# HIC_Board.net
KiCad netlist of a schematic drawn in EAGLE
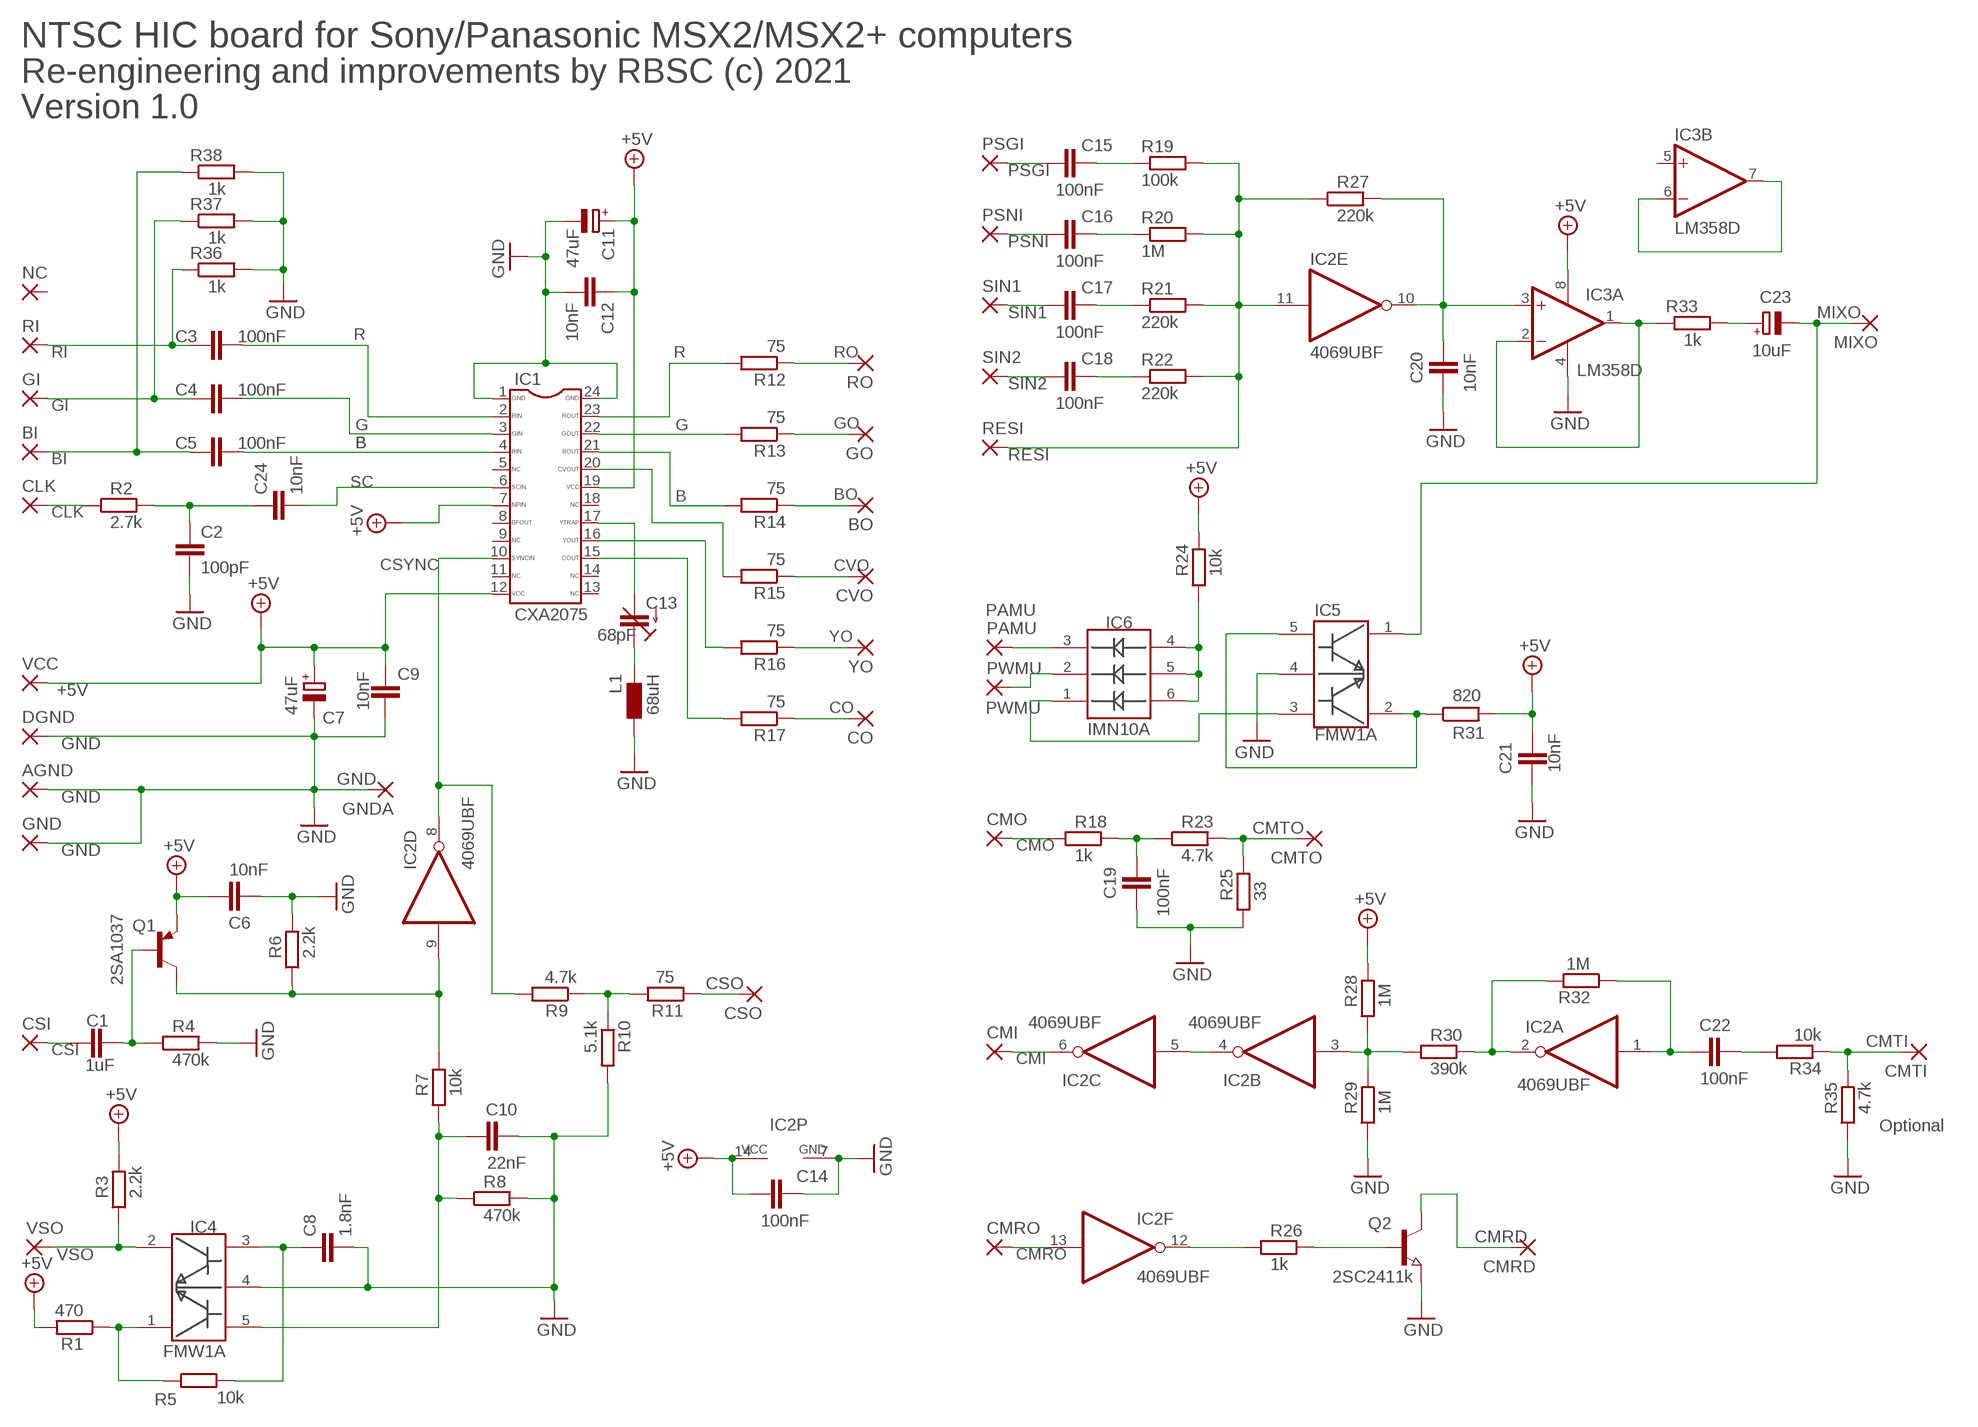
[diagram p0: schematic, sheet 1]

(export (version "E")
  (design (tool "Eeschema 10.0.6"))
  (components
    (comp (ref "AGND")
      (value "HICPADSMD")
      (footprint "eagle-import:SMD1,27-2,54")
      (libsource (lib "eagle-import") (part "HICPADSMD"))
    )
    (comp (ref "BI")
      (value "HICPADSMD")
      (footprint "eagle-import:SMD1,27-2,54")
      (libsource (lib "eagle-import") (part "HICPADSMD"))
    )
    (comp (ref "BO")
      (value "HICPADSMD")
      (footprint "eagle-import:SMD1,27-2,54")
      (libsource (lib "eagle-import") (part "HICPADSMD"))
    )
    (comp (ref "C1")
      (value "1uF")
      (footprint "eagle-import:C1210")
      (libsource (lib "eagle-import") (part "C-EUC1210"))
    )
    (comp (ref "C2")
      (value "100pF")
      (footprint "eagle-import:C0805")
      (libsource (lib "eagle-import") (part "C-EUC0805"))
    )
    (comp (ref "C3")
      (value "100nF")
      (footprint "eagle-import:C0805")
      (libsource (lib "eagle-import") (part "C-EUC0805"))
    )
    (comp (ref "C4")
      (value "100nF")
      (footprint "eagle-import:C0805")
      (libsource (lib "eagle-import") (part "C-EUC0805"))
    )
    (comp (ref "C5")
      (value "100nF")
      (footprint "eagle-import:C0805")
      (libsource (lib "eagle-import") (part "C-EUC0805"))
    )
    (comp (ref "C6")
      (value "10nF")
      (footprint "eagle-import:C0805")
      (libsource (lib "eagle-import") (part "C-EUC0805"))
    )
    (comp (ref "C7")
      (value "47uF")
      (footprint "eagle-import:SMC_B")
      (libsource (lib "eagle-import") (part "CPOL-EUSMCB"))
    )
    (comp (ref "C8")
      (value "1.8nF")
      (footprint "eagle-import:C0805")
      (libsource (lib "eagle-import") (part "C-EUC0805"))
    )
    (comp (ref "C9")
      (value "10nF")
      (footprint "eagle-import:C0805")
      (libsource (lib "eagle-import") (part "C-EUC0805"))
    )
    (comp (ref "C10")
      (value "22nF")
      (footprint "eagle-import:C0805")
      (libsource (lib "eagle-import") (part "C-EUC0805"))
    )
    (comp (ref "C11")
      (value "47uF")
      (footprint "eagle-import:SMC_B")
      (libsource (lib "eagle-import") (part "CPOL-EUSMCB"))
    )
    (comp (ref "C12")
      (value "10nF")
      (footprint "eagle-import:C0805")
      (libsource (lib "eagle-import") (part "C-EUC0805"))
    )
    (comp (ref "C13")
      (value "68pF")
      (footprint "eagle-import:CTRIMTZ03")
      (libsource (lib "eagle-import") (part "C-TRIMMTZ03"))
    )
    (comp (ref "C14")
      (value "100nF")
      (footprint "eagle-import:C0805")
      (libsource (lib "eagle-import") (part "C-EUC0805"))
    )
    (comp (ref "C15")
      (value "100nF")
      (footprint "eagle-import:C0805")
      (libsource (lib "eagle-import") (part "C-EUC0805"))
    )
    (comp (ref "C16")
      (value "100nF")
      (footprint "eagle-import:C0805")
      (libsource (lib "eagle-import") (part "C-EUC0805"))
    )
    (comp (ref "C17")
      (value "100nF")
      (footprint "eagle-import:C0805")
      (libsource (lib "eagle-import") (part "C-EUC0805"))
    )
    (comp (ref "C18")
      (value "100nF")
      (footprint "eagle-import:C0805")
      (libsource (lib "eagle-import") (part "C-EUC0805"))
    )
    (comp (ref "C19")
      (value "100nF")
      (footprint "eagle-import:C0805")
      (libsource (lib "eagle-import") (part "C-EUC0805"))
    )
    (comp (ref "C20")
      (value "10nF")
      (footprint "eagle-import:C0805")
      (libsource (lib "eagle-import") (part "C-EUC0805"))
    )
    (comp (ref "C21")
      (value "10nF")
      (footprint "eagle-import:C0805")
      (libsource (lib "eagle-import") (part "C-EUC0805"))
    )
    (comp (ref "C22")
      (value "100nF")
      (footprint "eagle-import:C0805")
      (libsource (lib "eagle-import") (part "C-EUC0805"))
    )
    (comp (ref "C23")
      (value "10uF")
      (footprint "eagle-import:SMC_B")
      (libsource (lib "eagle-import") (part "CPOL-EUSMCB"))
    )
    (comp (ref "C24")
      (value "10nF")
      (footprint "eagle-import:C0805")
      (libsource (lib "eagle-import") (part "C-EUC0805"))
    )
    (comp (ref "CLK")
      (value "HICPADSMD")
      (footprint "eagle-import:SMD1,27-2,54")
      (libsource (lib "eagle-import") (part "HICPADSMD"))
    )
    (comp (ref "CMI")
      (value "HICPADSMD")
      (footprint "eagle-import:SMD1,27-2,54")
      (libsource (lib "eagle-import") (part "HICPADSMD"))
    )
    (comp (ref "CMO")
      (value "HICPADSMD")
      (footprint "eagle-import:SMD1,27-2,54")
      (libsource (lib "eagle-import") (part "HICPADSMD"))
    )
    (comp (ref "CMRD")
      (value "HICPADSMD")
      (footprint "eagle-import:SMD1,27-2,54")
      (libsource (lib "eagle-import") (part "HICPADSMD"))
    )
    (comp (ref "CMRO")
      (value "HICPADSMD")
      (footprint "eagle-import:SMD1,27-2,54")
      (libsource (lib "eagle-import") (part "HICPADSMD"))
    )
    (comp (ref "CMTI")
      (value "HICPADSMD")
      (footprint "eagle-import:SMD1,27-2,54")
      (libsource (lib "eagle-import") (part "HICPADSMD"))
    )
    (comp (ref "CMTO")
      (value "HICPADSMD")
      (footprint "eagle-import:SMD1,27-2,54")
      (libsource (lib "eagle-import") (part "HICPADSMD"))
    )
    (comp (ref "CO")
      (value "HICPADSMD")
      (footprint "eagle-import:SMD1,27-2,54")
      (libsource (lib "eagle-import") (part "HICPADSMD"))
    )
    (comp (ref "CSI")
      (value "HICPADSMD")
      (footprint "eagle-import:SMD1,27-2,54")
      (libsource (lib "eagle-import") (part "HICPADSMD"))
    )
    (comp (ref "CSO")
      (value "HICPADSMD")
      (footprint "eagle-import:SMD1,27-2,54")
      (libsource (lib "eagle-import") (part "HICPADSMD"))
    )
    (comp (ref "CVO")
      (value "HICPADSMD")
      (footprint "eagle-import:SMD1,27-2,54")
      (libsource (lib "eagle-import") (part "HICPADSMD"))
    )
    (comp (ref "DGND")
      (value "HICPADSMD")
      (footprint "eagle-import:SMD1,27-2,54")
      (libsource (lib "eagle-import") (part "HICPADSMD"))
    )
    (comp (ref "GI")
      (value "HICPADSMD")
      (footprint "eagle-import:SMD1,27-2,54")
      (libsource (lib "eagle-import") (part "HICPADSMD"))
    )
    (comp (ref "GND")
      (value "HICPADSMD")
      (footprint "eagle-import:SMD1,27-2,54")
      (libsource (lib "eagle-import") (part "HICPADSMD"))
    )
    (comp (ref "GNDA")
      (value "HICPADSMD")
      (footprint "eagle-import:SMD1,27-2,54")
      (libsource (lib "eagle-import") (part "HICPADSMD"))
    )
    (comp (ref "GO")
      (value "HICPADSMD")
      (footprint "eagle-import:SMD1,27-2,54")
      (libsource (lib "eagle-import") (part "HICPADSMD"))
    )
    (comp (ref "IC1")
      (value "CXA2075")
      (footprint "eagle-import:SOP24")
      (libsource (lib "eagle-import") (part "CXA2075"))
    )
    (comp (ref "IC2")
      (value "4069UBF")
      (footprint "eagle-import:SO14")
      (libsource (lib "eagle-import") (part "7404DHCT"))
    )
    (comp (ref "IC3")
      (value "LM358D")
      (footprint "eagle-import:SO08")
      (libsource (lib "eagle-import") (part "LM358D"))
    )
    (comp (ref "IC4")
      (value "FMW1A")
      (footprint "eagle-import:SMT5")
      (libsource (lib "eagle-import") (part "FMW1A"))
    )
    (comp (ref "IC5")
      (value "FMW1A")
      (footprint "eagle-import:SMT5")
      (libsource (lib "eagle-import") (part "FMW1A"))
    )
    (comp (ref "IC6")
      (value "IMN10A")
      (footprint "eagle-import:SMT6")
      (libsource (lib "eagle-import") (part "IMN10A"))
    )
    (comp (ref "L1")
      (value "68uH")
      (footprint "eagle-import:L3225M")
      (libsource (lib "eagle-import") (part "LL3225M"))
    )
    (comp (ref "MIXO")
      (value "HICPADSMD")
      (footprint "eagle-import:SMD1,27-2,54")
      (libsource (lib "eagle-import") (part "HICPADSMD"))
    )
    (comp (ref "NC")
      (value "HICPADSMD")
      (footprint "eagle-import:SMD1,27-2,54")
      (libsource (lib "eagle-import") (part "HICPADSMD"))
    )
    (comp (ref "PAMU")
      (value "HICPADSMD")
      (footprint "eagle-import:SMD1,27-2,54")
      (libsource (lib "eagle-import") (part "HICPADSMD"))
    )
    (comp (ref "PSGI")
      (value "HICPADSMD")
      (footprint "eagle-import:SMD1,27-2,54")
      (libsource (lib "eagle-import") (part "HICPADSMD"))
    )
    (comp (ref "PSNI")
      (value "HICPADSMD")
      (footprint "eagle-import:SMD1,27-2,54")
      (libsource (lib "eagle-import") (part "HICPADSMD"))
    )
    (comp (ref "PWMU")
      (value "HICPADSMD")
      (footprint "eagle-import:SMD1,27-2,54")
      (libsource (lib "eagle-import") (part "HICPADSMD"))
    )
    (comp (ref "Q1")
      (value "2SA1037")
      (footprint "eagle-import:SOT23")
      (libsource (lib "eagle-import") (part "BCX71SMD"))
    )
    (comp (ref "Q2")
      (value "2SC2411k")
      (footprint "eagle-import:SOT23")
      (libsource (lib "eagle-import") (part "NPN-TRANSISTOR_SOT23"))
    )
    (comp (ref "R1")
      (value "470")
      (footprint "eagle-import:R0805")
      (libsource (lib "eagle-import") (part "R-EU_R0805"))
    )
    (comp (ref "R2")
      (value "2.7k")
      (footprint "eagle-import:R0805")
      (libsource (lib "eagle-import") (part "R-EU_R0805"))
    )
    (comp (ref "R3")
      (value "2.2k")
      (footprint "eagle-import:R0805")
      (libsource (lib "eagle-import") (part "R-EU_R0805"))
    )
    (comp (ref "R4")
      (value "470k")
      (footprint "eagle-import:R0805")
      (libsource (lib "eagle-import") (part "R-EU_R0805"))
    )
    (comp (ref "R5")
      (value "10k")
      (footprint "eagle-import:R0805")
      (libsource (lib "eagle-import") (part "R-EU_R0805"))
    )
    (comp (ref "R6")
      (value "2.2k")
      (footprint "eagle-import:R0805")
      (libsource (lib "eagle-import") (part "R-EU_R0805"))
    )
    (comp (ref "R7")
      (value "10k")
      (footprint "eagle-import:R0805")
      (libsource (lib "eagle-import") (part "R-EU_R0805"))
    )
    (comp (ref "R8")
      (value "470k")
      (footprint "eagle-import:R0805")
      (libsource (lib "eagle-import") (part "R-EU_R0805"))
    )
    (comp (ref "R9")
      (value "4.7k")
      (footprint "eagle-import:R0805")
      (libsource (lib "eagle-import") (part "R-EU_R0805"))
    )
    (comp (ref "R10")
      (value "5.1k")
      (footprint "eagle-import:R0805")
      (libsource (lib "eagle-import") (part "R-EU_R0805"))
    )
    (comp (ref "R11")
      (value "75")
      (footprint "eagle-import:R0805")
      (libsource (lib "eagle-import") (part "R-EU_R0805"))
    )
    (comp (ref "R12")
      (value "75")
      (footprint "eagle-import:R0805")
      (libsource (lib "eagle-import") (part "R-EU_R0805"))
    )
    (comp (ref "R13")
      (value "75")
      (footprint "eagle-import:R0805")
      (libsource (lib "eagle-import") (part "R-EU_R0805"))
    )
    (comp (ref "R14")
      (value "75")
      (footprint "eagle-import:R0805")
      (libsource (lib "eagle-import") (part "R-EU_R0805"))
    )
    (comp (ref "R15")
      (value "75")
      (footprint "eagle-import:R0805")
      (libsource (lib "eagle-import") (part "R-EU_R0805"))
    )
    (comp (ref "R16")
      (value "75")
      (footprint "eagle-import:R0805")
      (libsource (lib "eagle-import") (part "R-EU_R0805"))
    )
    (comp (ref "R17")
      (value "75")
      (footprint "eagle-import:R0805")
      (libsource (lib "eagle-import") (part "R-EU_R0805"))
    )
    (comp (ref "R18")
      (value "1k")
      (footprint "eagle-import:R0805")
      (libsource (lib "eagle-import") (part "R-EU_R0805"))
    )
    (comp (ref "R19")
      (value "100k")
      (footprint "eagle-import:R0805")
      (libsource (lib "eagle-import") (part "R-EU_R0805"))
    )
    (comp (ref "R20")
      (value "1M")
      (footprint "eagle-import:R0805")
      (libsource (lib "eagle-import") (part "R-EU_R0805"))
    )
    (comp (ref "R21")
      (value "220k")
      (footprint "eagle-import:R0805")
      (libsource (lib "eagle-import") (part "R-EU_R0805"))
    )
    (comp (ref "R22")
      (value "220k")
      (footprint "eagle-import:R0805")
      (libsource (lib "eagle-import") (part "R-EU_R0805"))
    )
    (comp (ref "R23")
      (value "4.7k")
      (footprint "eagle-import:R0805")
      (libsource (lib "eagle-import") (part "R-EU_R0805"))
    )
    (comp (ref "R24")
      (value "10k")
      (footprint "eagle-import:R0805")
      (libsource (lib "eagle-import") (part "R-EU_R0805"))
    )
    (comp (ref "R25")
      (value "33")
      (footprint "eagle-import:R0805")
      (libsource (lib "eagle-import") (part "R-EU_R0805"))
    )
    (comp (ref "R26")
      (value "1k")
      (footprint "eagle-import:R0805")
      (libsource (lib "eagle-import") (part "R-EU_R0805"))
    )
    (comp (ref "R27")
      (value "220k")
      (footprint "eagle-import:R0805")
      (libsource (lib "eagle-import") (part "R-EU_R0805"))
    )
    (comp (ref "R28")
      (value "1M")
      (footprint "eagle-import:R0805")
      (libsource (lib "eagle-import") (part "R-EU_R0805"))
    )
    (comp (ref "R29")
      (value "1M")
      (footprint "eagle-import:R0805")
      (libsource (lib "eagle-import") (part "R-EU_R0805"))
    )
    (comp (ref "R30")
      (value "390k")
      (footprint "eagle-import:R0805")
      (libsource (lib "eagle-import") (part "R-EU_R0805"))
    )
    (comp (ref "R31")
      (value "820")
      (footprint "eagle-import:R0805")
      (libsource (lib "eagle-import") (part "R-EU_R0805"))
    )
    (comp (ref "R32")
      (value "1M")
      (footprint "eagle-import:R0805")
      (libsource (lib "eagle-import") (part "R-EU_R0805"))
    )
    (comp (ref "R33")
      (value "1k")
      (footprint "eagle-import:R0805")
      (libsource (lib "eagle-import") (part "R-EU_R0805"))
    )
    (comp (ref "R34")
      (value "10k")
      (footprint "eagle-import:R0805")
      (libsource (lib "eagle-import") (part "R-EU_R0805"))
    )
    (comp (ref "R35")
      (value "4.7k")
      (footprint "eagle-import:R0805")
      (libsource (lib "eagle-import") (part "R-EU_R0805"))
    )
    (comp (ref "R36")
      (value "1k")
      (footprint "eagle-import:R0805")
      (libsource (lib "eagle-import") (part "R-EU_R0805"))
    )
    (comp (ref "R37")
      (value "1k")
      (footprint "eagle-import:R0805")
      (libsource (lib "eagle-import") (part "R-EU_R0805"))
    )
    (comp (ref "R38")
      (value "1k")
      (footprint "eagle-import:R0805")
      (libsource (lib "eagle-import") (part "R-EU_R0805"))
    )
    (comp (ref "RESI")
      (value "HICPADSMD")
      (footprint "eagle-import:SMD1,27-2,54")
      (libsource (lib "eagle-import") (part "HICPADSMD"))
    )
    (comp (ref "RI")
      (value "HICPADSMD")
      (footprint "eagle-import:SMD1,27-2,54")
      (libsource (lib "eagle-import") (part "HICPADSMD"))
    )
    (comp (ref "RO")
      (value "HICPADSMD")
      (footprint "eagle-import:SMD1,27-2,54")
      (libsource (lib "eagle-import") (part "HICPADSMD"))
    )
    (comp (ref "SIN1")
      (value "HICPADSMD")
      (footprint "eagle-import:SMD1,27-2,54")
      (libsource (lib "eagle-import") (part "HICPADSMD"))
    )
    (comp (ref "SIN2")
      (value "HICPADSMD")
      (footprint "eagle-import:SMD1,27-2,54")
      (libsource (lib "eagle-import") (part "HICPADSMD"))
    )
    (comp (ref "VCC")
      (value "HICPADSMD")
      (footprint "eagle-import:SMD1,27-2,54")
      (libsource (lib "eagle-import") (part "HICPADSMD"))
    )
    (comp (ref "VSO")
      (value "HICPADSMD")
      (footprint "eagle-import:SMD1,27-2,54")
      (libsource (lib "eagle-import") (part "HICPADSMD"))
    )
    (comp (ref "YO")
      (value "HICPADSMD")
      (footprint "eagle-import:SMD1,27-2,54")
      (libsource (lib "eagle-import") (part "HICPADSMD"))
    )
  )
  (nets
    (net (code "1") (name "+5V") (class "Default")
      (node (ref "C11") (pin "+") (pinfunction "+_+") (pintype "passive"))
      (node (ref "C12") (pin "1") (pinfunction "1_1") (pintype "passive"))
      (node (ref "C14") (pin "2") (pinfunction "2_2") (pintype "passive"))
      (node (ref "C21") (pin "2") (pinfunction "2_2") (pintype "passive"))
      (node (ref "C6") (pin "1") (pinfunction "1_1") (pintype "passive"))
      (node (ref "C7") (pin "+") (pinfunction "+_+") (pintype "passive"))
      (node (ref "C9") (pin "2") (pinfunction "2_2") (pintype "passive"))
      (node (ref "IC1") (pin "12") (pinfunction "12_12") (pintype "passive"))
      (node (ref "IC1") (pin "19") (pinfunction "19_19") (pintype "passive"))
      (node (ref "IC1") (pin "7") (pinfunction "7_7") (pintype "passive"))
      (node (ref "IC2") (pin "14") (pinfunction "VCC_14") (pintype "power_in"))
      (node (ref "IC3") (pin "8") (pinfunction "V+_8") (pintype "power_in"))
      (node (ref "Q1") (pin "2") (pinfunction "E_2") (pintype "passive"))
      (node (ref "R1") (pin "2") (pinfunction "2_2") (pintype "passive"))
      (node (ref "R24") (pin "2") (pinfunction "2_2") (pintype "passive"))
      (node (ref "R28") (pin "2") (pinfunction "2_2") (pintype "passive"))
      (node (ref "R3") (pin "2") (pinfunction "2_2") (pintype "passive"))
      (node (ref "R31") (pin "2") (pinfunction "2_2") (pintype "passive"))
      (node (ref "VCC") (pin "1") (pinfunction "P_1") (pintype "bidirectional"))
    )
    (net (code "2") (name "/CMRD") (class "Default")
      (node (ref "CMRD") (pin "1") (pinfunction "P_1") (pintype "bidirectional"))
      (node (ref "Q2") (pin "3") (pinfunction "C_3") (pintype "passive"))
    )
    (net (code "3") (name "/CMTI") (class "Default")
      (node (ref "CMTI") (pin "1") (pinfunction "P_1") (pintype "bidirectional"))
      (node (ref "R34") (pin "1") (pinfunction "1_1") (pintype "passive"))
      (node (ref "R35") (pin "2") (pinfunction "2_2") (pintype "passive"))
    )
    (net (code "4") (name "/CMTO") (class "Default")
      (node (ref "CMTO") (pin "1") (pinfunction "P_1") (pintype "bidirectional"))
      (node (ref "R23") (pin "2") (pinfunction "2_2") (pintype "passive"))
      (node (ref "R25") (pin "2") (pinfunction "2_2") (pintype "passive"))
    )
    (net (code "5") (name "/CSO") (class "Default")
      (node (ref "CSO") (pin "1") (pinfunction "P_1") (pintype "bidirectional"))
      (node (ref "R11") (pin "1") (pinfunction "1_1") (pintype "passive"))
    )
    (net (code "6") (name "/MIXO") (class "Default")
      (node (ref "C23") (pin "-") (pinfunction "-_-") (pintype "passive"))
      (node (ref "IC5") (pin "1") (pinfunction "P$1_1") (pintype "bidirectional"))
      (node (ref "MIXO") (pin "1") (pinfunction "P_1") (pintype "bidirectional"))
    )
    (net (code "7") (name "/PAMU") (class "Default")
      (node (ref "IC6") (pin "3") (pinfunction "P$3_3") (pintype "bidirectional"))
      (node (ref "PAMU") (pin "1") (pinfunction "P_1") (pintype "bidirectional"))
    )
    (net (code "8") (name "/PSGI") (class "Default")
      (node (ref "C15") (pin "1") (pinfunction "1_1") (pintype "passive"))
      (node (ref "PSGI") (pin "1") (pinfunction "P_1") (pintype "bidirectional"))
    )
    (net (code "9") (name "/PSNI") (class "Default")
      (node (ref "C16") (pin "1") (pinfunction "1_1") (pintype "passive"))
      (node (ref "PSNI") (pin "1") (pinfunction "P_1") (pintype "bidirectional"))
    )
    (net (code "10") (name "/PWMU") (class "Default")
      (node (ref "IC6") (pin "2") (pinfunction "P$2_2") (pintype "bidirectional"))
      (node (ref "PWMU") (pin "1") (pinfunction "P_1") (pintype "bidirectional"))
    )
    (net (code "11") (name "/RESI") (class "Default")
      (node (ref "IC2") (pin "11") (pinfunction "I_11") (pintype "input"))
      (node (ref "R19") (pin "2") (pinfunction "2_2") (pintype "passive"))
      (node (ref "R20") (pin "2") (pinfunction "2_2") (pintype "passive"))
      (node (ref "R21") (pin "2") (pinfunction "2_2") (pintype "passive"))
      (node (ref "R22") (pin "2") (pinfunction "2_2") (pintype "passive"))
      (node (ref "R27") (pin "1") (pinfunction "1_1") (pintype "passive"))
      (node (ref "RESI") (pin "1") (pinfunction "P_1") (pintype "bidirectional"))
    )
    (net (code "12") (name "/SIN1") (class "Default")
      (node (ref "C17") (pin "1") (pinfunction "1_1") (pintype "passive"))
      (node (ref "SIN1") (pin "1") (pinfunction "P_1") (pintype "bidirectional"))
    )
    (net (code "13") (name "/SIN2") (class "Default")
      (node (ref "C18") (pin "1") (pinfunction "1_1") (pintype "passive"))
      (node (ref "SIN2") (pin "1") (pinfunction "P_1") (pintype "bidirectional"))
    )
    (net (code "14") (name "/VSO") (class "Default")
      (node (ref "IC4") (pin "2") (pinfunction "P$2_2") (pintype "bidirectional"))
      (node (ref "R3") (pin "1") (pinfunction "1_1") (pintype "passive"))
      (node (ref "VSO") (pin "1") (pinfunction "P_1") (pintype "bidirectional"))
    )
    (net (code "15") (name "GND") (class "Default")
      (node (ref "AGND") (pin "1") (pinfunction "P_1") (pintype "bidirectional"))
      (node (ref "C10") (pin "2") (pinfunction "2_2") (pintype "passive"))
      (node (ref "C11") (pin "-") (pinfunction "-_-") (pintype "passive"))
      (node (ref "C12") (pin "2") (pinfunction "2_2") (pintype "passive"))
      (node (ref "C14") (pin "1") (pinfunction "1_1") (pintype "passive"))
      (node (ref "C19") (pin "2") (pinfunction "2_2") (pintype "passive"))
      (node (ref "C2") (pin "1") (pinfunction "1_1") (pintype "passive"))
      (node (ref "C20") (pin "2") (pinfunction "2_2") (pintype "passive"))
      (node (ref "C21") (pin "1") (pinfunction "1_1") (pintype "passive"))
      (node (ref "C6") (pin "2") (pinfunction "2_2") (pintype "passive"))
      (node (ref "C7") (pin "-") (pinfunction "-_-") (pintype "passive"))
      (node (ref "C8") (pin "1") (pinfunction "1_1") (pintype "passive"))
      (node (ref "C9") (pin "1") (pinfunction "1_1") (pintype "passive"))
      (node (ref "DGND") (pin "1") (pinfunction "P_1") (pintype "bidirectional"))
      (node (ref "GND") (pin "1") (pinfunction "P_1") (pintype "bidirectional"))
      (node (ref "GNDA") (pin "1") (pinfunction "P_1") (pintype "bidirectional"))
      (node (ref "IC1") (pin "1") (pinfunction "1_1") (pintype "passive"))
      (node (ref "IC1") (pin "24") (pinfunction "24_24") (pintype "passive"))
      (node (ref "IC2") (pin "7") (pinfunction "GND_7") (pintype "power_in"))
      (node (ref "IC3") (pin "4") (pinfunction "V-_4") (pintype "power_in"))
      (node (ref "IC4") (pin "4") (pinfunction "P$4_4") (pintype "bidirectional"))
      (node (ref "IC5") (pin "4") (pinfunction "P$4_4") (pintype "bidirectional"))
      (node (ref "L1") (pin "1") (pinfunction "1_1") (pintype "passive"))
      (node (ref "Q2") (pin "2") (pinfunction "E_2") (pintype "passive"))
      (node (ref "R10") (pin "2") (pinfunction "2_2") (pintype "passive"))
      (node (ref "R25") (pin "1") (pinfunction "1_1") (pintype "passive"))
      (node (ref "R29") (pin "1") (pinfunction "1_1") (pintype "passive"))
      (node (ref "R35") (pin "1") (pinfunction "1_1") (pintype "passive"))
      (node (ref "R36") (pin "2") (pinfunction "2_2") (pintype "passive"))
      (node (ref "R37") (pin "2") (pinfunction "2_2") (pintype "passive"))
      (node (ref "R38") (pin "2") (pinfunction "2_2") (pintype "passive"))
      (node (ref "R4") (pin "2") (pinfunction "2_2") (pintype "passive"))
      (node (ref "R6") (pin "2") (pinfunction "2_2") (pintype "passive"))
      (node (ref "R8") (pin "2") (pinfunction "2_2") (pintype "passive"))
    )
    (net (code "16") (name "Net-(BI-P)") (class "Default")
      (node (ref "BI") (pin "1") (pinfunction "P_1") (pintype "bidirectional"))
      (node (ref "C5") (pin "1") (pinfunction "1_1") (pintype "passive"))
      (node (ref "R38") (pin "1") (pinfunction "1_1") (pintype "passive"))
    )
    (net (code "17") (name "Net-(BO-P)") (class "Default")
      (node (ref "BO") (pin "1") (pinfunction "P_1") (pintype "bidirectional"))
      (node (ref "R14") (pin "1") (pinfunction "1_1") (pintype "passive"))
    )
    (net (code "18") (name "Net-(C2-Pad2)") (class "Default")
      (node (ref "C2") (pin "2") (pinfunction "2_2") (pintype "passive"))
      (node (ref "C24") (pin "2") (pinfunction "2_2") (pintype "passive"))
      (node (ref "R2") (pin "2") (pinfunction "2_2") (pintype "passive"))
    )
    (net (code "19") (name "Net-(C3-Pad2)") (class "Default")
      (node (ref "C3") (pin "2") (pinfunction "2_2") (pintype "passive"))
      (node (ref "IC1") (pin "2") (pinfunction "2_2") (pintype "passive"))
    )
    (net (code "20") (name "Net-(C4-Pad2)") (class "Default")
      (node (ref "C4") (pin "2") (pinfunction "2_2") (pintype "passive"))
      (node (ref "IC1") (pin "3") (pinfunction "3_3") (pintype "passive"))
    )
    (net (code "21") (name "Net-(C5-Pad2)") (class "Default")
      (node (ref "C5") (pin "2") (pinfunction "2_2") (pintype "passive"))
      (node (ref "IC1") (pin "4") (pinfunction "4_4") (pintype "passive"))
    )
    (net (code "22") (name "Net-(C13-A)") (class "Default")
      (node (ref "C13") (pin "2") (pinfunction "A_2") (pintype "passive"))
      (node (ref "IC1") (pin "17") (pinfunction "17_17") (pintype "passive"))
    )
    (net (code "23") (name "Net-(C13-E)") (class "Default")
      (node (ref "C13") (pin "1") (pinfunction "E_1") (pintype "passive"))
      (node (ref "L1") (pin "2") (pinfunction "2_2") (pintype "passive"))
    )
    (net (code "24") (name "Net-(C15-Pad2)") (class "Default")
      (node (ref "C15") (pin "2") (pinfunction "2_2") (pintype "passive"))
      (node (ref "R19") (pin "1") (pinfunction "1_1") (pintype "passive"))
    )
    (net (code "25") (name "Net-(C16-Pad2)") (class "Default")
      (node (ref "C16") (pin "2") (pinfunction "2_2") (pintype "passive"))
      (node (ref "R20") (pin "1") (pinfunction "1_1") (pintype "passive"))
    )
    (net (code "26") (name "Net-(C17-Pad2)") (class "Default")
      (node (ref "C17") (pin "2") (pinfunction "2_2") (pintype "passive"))
      (node (ref "R21") (pin "1") (pinfunction "1_1") (pintype "passive"))
    )
    (net (code "27") (name "Net-(C18-Pad2)") (class "Default")
      (node (ref "C18") (pin "2") (pinfunction "2_2") (pintype "passive"))
      (node (ref "R22") (pin "1") (pinfunction "1_1") (pintype "passive"))
    )
    (net (code "28") (name "Net-(C19-Pad1)") (class "Default")
      (node (ref "C19") (pin "1") (pinfunction "1_1") (pintype "passive"))
      (node (ref "R18") (pin "2") (pinfunction "2_2") (pintype "passive"))
      (node (ref "R23") (pin "1") (pinfunction "1_1") (pintype "passive"))
    )
    (net (code "29") (name "Net-(C22-Pad2)") (class "Default")
      (node (ref "C22") (pin "2") (pinfunction "2_2") (pintype "passive"))
      (node (ref "R34") (pin "2") (pinfunction "2_2") (pintype "passive"))
    )
    (net (code "30") (name "Net-(C23-Pad+)") (class "Default")
      (node (ref "C23") (pin "+") (pinfunction "+_+") (pintype "passive"))
      (node (ref "R33") (pin "2") (pinfunction "2_2") (pintype "passive"))
    )
    (net (code "31") (name "Net-(C24-Pad1)") (class "Default")
      (node (ref "C24") (pin "1") (pinfunction "1_1") (pintype "passive"))
      (node (ref "IC1") (pin "6") (pinfunction "6_6") (pintype "passive"))
    )
    (net (code "32") (name "Net-(CLK-P)") (class "Default")
      (node (ref "CLK") (pin "1") (pinfunction "P_1") (pintype "bidirectional"))
      (node (ref "R2") (pin "1") (pinfunction "1_1") (pintype "passive"))
    )
    (net (code "33") (name "Net-(CMI-P)") (class "Default")
      (node (ref "CMI") (pin "1") (pinfunction "P_1") (pintype "bidirectional"))
      (node (ref "IC2") (pin "6") (pinfunction "O_6") (pintype "output"))
    )
    (net (code "34") (name "Net-(CMO-P)") (class "Default")
      (node (ref "CMO") (pin "1") (pinfunction "P_1") (pintype "bidirectional"))
      (node (ref "R18") (pin "1") (pinfunction "1_1") (pintype "passive"))
    )
    (net (code "35") (name "Net-(CMRO-P)") (class "Default")
      (node (ref "CMRO") (pin "1") (pinfunction "P_1") (pintype "bidirectional"))
      (node (ref "IC2") (pin "13") (pinfunction "I_13") (pintype "input"))
    )
    (net (code "36") (name "Net-(CO-P)") (class "Default")
      (node (ref "CO") (pin "1") (pinfunction "P_1") (pintype "bidirectional"))
      (node (ref "R17") (pin "1") (pinfunction "1_1") (pintype "passive"))
    )
    (net (code "37") (name "Net-(CSI-P)") (class "Default")
      (node (ref "C1") (pin "2") (pinfunction "2_2") (pintype "passive"))
      (node (ref "CSI") (pin "1") (pinfunction "P_1") (pintype "bidirectional"))
    )
    (net (code "38") (name "Net-(CVO-P)") (class "Default")
      (node (ref "CVO") (pin "1") (pinfunction "P_1") (pintype "bidirectional"))
      (node (ref "R15") (pin "1") (pinfunction "1_1") (pintype "passive"))
    )
    (net (code "39") (name "Net-(GI-P)") (class "Default")
      (node (ref "C4") (pin "1") (pinfunction "1_1") (pintype "passive"))
      (node (ref "GI") (pin "1") (pinfunction "P_1") (pintype "bidirectional"))
      (node (ref "R37") (pin "1") (pinfunction "1_1") (pintype "passive"))
    )
    (net (code "40") (name "Net-(GO-P)") (class "Default")
      (node (ref "GO") (pin "1") (pinfunction "P_1") (pintype "bidirectional"))
      (node (ref "R13") (pin "1") (pinfunction "1_1") (pintype "passive"))
    )
    (net (code "41") (name "Net-(IC1-Pad15)") (class "Default")
      (node (ref "IC1") (pin "15") (pinfunction "15_15") (pintype "passive"))
      (node (ref "R17") (pin "2") (pinfunction "2_2") (pintype "passive"))
    )
    (net (code "42") (name "Net-(IC1-Pad16)") (class "Default")
      (node (ref "IC1") (pin "16") (pinfunction "16_16") (pintype "passive"))
      (node (ref "R16") (pin "2") (pinfunction "2_2") (pintype "passive"))
    )
    (net (code "43") (name "Net-(IC1-Pad20)") (class "Default")
      (node (ref "IC1") (pin "20") (pinfunction "20_20") (pintype "passive"))
      (node (ref "R15") (pin "2") (pinfunction "2_2") (pintype "passive"))
    )
    (net (code "44") (name "Net-(IC1-Pad21)") (class "Default")
      (node (ref "IC1") (pin "21") (pinfunction "21_21") (pintype "passive"))
      (node (ref "R14") (pin "2") (pinfunction "2_2") (pintype "passive"))
    )
    (net (code "45") (name "Net-(IC1-Pad22)") (class "Default")
      (node (ref "IC1") (pin "22") (pinfunction "22_22") (pintype "passive"))
      (node (ref "R13") (pin "2") (pinfunction "2_2") (pintype "passive"))
    )
    (net (code "46") (name "Net-(IC1-Pad23)") (class "Default")
      (node (ref "IC1") (pin "23") (pinfunction "23_23") (pintype "passive"))
      (node (ref "R12") (pin "2") (pinfunction "2_2") (pintype "passive"))
    )
    (net (code "47") (name "Net-(IC2A-I)") (class "Default")
      (node (ref "C22") (pin "1") (pinfunction "1_1") (pintype "passive"))
      (node (ref "IC2") (pin "1") (pinfunction "I_1") (pintype "input"))
      (node (ref "R32") (pin "1") (pinfunction "1_1") (pintype "passive"))
    )
    (net (code "48") (name "Net-(IC2A-O)") (class "Default")
      (node (ref "IC2") (pin "2") (pinfunction "O_2") (pintype "output"))
      (node (ref "R30") (pin "2") (pinfunction "2_2") (pintype "passive"))
      (node (ref "R32") (pin "2") (pinfunction "2_2") (pintype "passive"))
    )
    (net (code "49") (name "Net-(IC2B-I)") (class "Default")
      (node (ref "IC2") (pin "3") (pinfunction "I_3") (pintype "input"))
      (node (ref "R28") (pin "1") (pinfunction "1_1") (pintype "passive"))
      (node (ref "R29") (pin "2") (pinfunction "2_2") (pintype "passive"))
      (node (ref "R30") (pin "1") (pinfunction "1_1") (pintype "passive"))
    )
    (net (code "50") (name "Net-(IC2B-O)") (class "Default")
      (node (ref "IC2") (pin "4") (pinfunction "O_4") (pintype "output"))
      (node (ref "IC2") (pin "5") (pinfunction "I_5") (pintype "input"))
    )
    (net (code "51") (name "Net-(IC2D-I)") (class "Default")
      (node (ref "IC2") (pin "9") (pinfunction "I_9") (pintype "input"))
      (node (ref "Q1") (pin "3") (pinfunction "C_3") (pintype "passive"))
      (node (ref "R6") (pin "1") (pinfunction "1_1") (pintype "passive"))
      (node (ref "R7") (pin "2") (pinfunction "2_2") (pintype "passive"))
    )
    (net (code "52") (name "Net-(IC2D-O)") (class "Default")
      (node (ref "IC1") (pin "10") (pinfunction "10_10") (pintype "passive"))
      (node (ref "IC2") (pin "8") (pinfunction "O_8") (pintype "output"))
      (node (ref "R9") (pin "2") (pinfunction "2_2") (pintype "passive"))
    )
    (net (code "53") (name "Net-(IC2E-O)") (class "Default")
      (node (ref "C20") (pin "1") (pinfunction "1_1") (pintype "passive"))
      (node (ref "IC2") (pin "10") (pinfunction "O_10") (pintype "output"))
      (node (ref "IC3") (pin "3") (pinfunction "+IN_3") (pintype "input"))
      (node (ref "R27") (pin "2") (pinfunction "2_2") (pintype "passive"))
    )
    (net (code "54") (name "Net-(IC2F-O)") (class "Default")
      (node (ref "IC2") (pin "12") (pinfunction "O_12") (pintype "output"))
      (node (ref "R26") (pin "1") (pinfunction "1_1") (pintype "passive"))
    )
    (net (code "55") (name "Net-(IC3A--IN)") (class "Default")
      (node (ref "IC3") (pin "1") (pinfunction "OUT_1") (pintype "output"))
      (node (ref "IC3") (pin "2") (pinfunction "-IN_2") (pintype "input"))
      (node (ref "R33") (pin "1") (pinfunction "1_1") (pintype "passive"))
    )
    (net (code "56") (name "Net-(IC3B--IN)") (class "Default")
      (node (ref "IC3") (pin "6") (pinfunction "-IN_6") (pintype "input"))
      (node (ref "IC3") (pin "7") (pinfunction "OUT_7") (pintype "output"))
    )
    (net (code "57") (name "Net-(IC4-P$1)") (class "Default")
      (node (ref "IC4") (pin "1") (pinfunction "P$1_1") (pintype "bidirectional"))
      (node (ref "R1") (pin "1") (pinfunction "1_1") (pintype "passive"))
      (node (ref "R5") (pin "1") (pinfunction "1_1") (pintype "passive"))
    )
    (net (code "58") (name "Net-(IC4-P$3)") (class "Default")
      (node (ref "C8") (pin "2") (pinfunction "2_2") (pintype "passive"))
      (node (ref "IC4") (pin "3") (pinfunction "P$3_3") (pintype "bidirectional"))
      (node (ref "R5") (pin "2") (pinfunction "2_2") (pintype "passive"))
    )
    (net (code "59") (name "Net-(IC4-P$5)") (class "Default")
      (node (ref "C10") (pin "1") (pinfunction "1_1") (pintype "passive"))
      (node (ref "IC4") (pin "5") (pinfunction "P$5_5") (pintype "bidirectional"))
      (node (ref "R7") (pin "1") (pinfunction "1_1") (pintype "passive"))
      (node (ref "R8") (pin "1") (pinfunction "1_1") (pintype "passive"))
    )
    (net (code "60") (name "Net-(IC5-P$2)") (class "Default")
      (node (ref "IC5") (pin "2") (pinfunction "P$2_2") (pintype "bidirectional"))
      (node (ref "IC5") (pin "5") (pinfunction "P$5_5") (pintype "bidirectional"))
      (node (ref "R31") (pin "1") (pinfunction "1_1") (pintype "passive"))
    )
    (net (code "61") (name "Net-(IC5-P$3)") (class "Default")
      (node (ref "IC5") (pin "3") (pinfunction "P$3_3") (pintype "bidirectional"))
      (node (ref "IC6") (pin "1") (pinfunction "P$1_1") (pintype "bidirectional"))
    )
    (net (code "62") (name "Net-(IC6-P$4)") (class "Default")
      (node (ref "IC6") (pin "4") (pinfunction "P$4_4") (pintype "bidirectional"))
      (node (ref "IC6") (pin "5") (pinfunction "P$5_5") (pintype "bidirectional"))
      (node (ref "IC6") (pin "6") (pinfunction "P$6_6") (pintype "bidirectional"))
      (node (ref "R24") (pin "1") (pinfunction "1_1") (pintype "passive"))
    )
    (net (code "63") (name "Net-(Q1-B)") (class "Default")
      (node (ref "C1") (pin "1") (pinfunction "1_1") (pintype "passive"))
      (node (ref "Q1") (pin "1") (pinfunction "B_1") (pintype "passive"))
      (node (ref "R4") (pin "1") (pinfunction "1_1") (pintype "passive"))
    )
    (net (code "64") (name "Net-(Q2-B)") (class "Default")
      (node (ref "Q2") (pin "1") (pinfunction "B_1") (pintype "passive"))
      (node (ref "R26") (pin "2") (pinfunction "2_2") (pintype "passive"))
    )
    (net (code "65") (name "Net-(R10-Pad1)") (class "Default")
      (node (ref "R10") (pin "1") (pinfunction "1_1") (pintype "passive"))
      (node (ref "R11") (pin "2") (pinfunction "2_2") (pintype "passive"))
      (node (ref "R9") (pin "1") (pinfunction "1_1") (pintype "passive"))
    )
    (net (code "66") (name "Net-(RI-P)") (class "Default")
      (node (ref "C3") (pin "1") (pinfunction "1_1") (pintype "passive"))
      (node (ref "R36") (pin "1") (pinfunction "1_1") (pintype "passive"))
      (node (ref "RI") (pin "1") (pinfunction "P_1") (pintype "bidirectional"))
    )
    (net (code "67") (name "Net-(RO-P)") (class "Default")
      (node (ref "R12") (pin "1") (pinfunction "1_1") (pintype "passive"))
      (node (ref "RO") (pin "1") (pinfunction "P_1") (pintype "bidirectional"))
    )
    (net (code "68") (name "Net-(YO-P)") (class "Default")
      (node (ref "R16") (pin "1") (pinfunction "1_1") (pintype "passive"))
      (node (ref "YO") (pin "1") (pinfunction "P_1") (pintype "bidirectional"))
    )
    (net (code "69") (name "unconnected-(IC1-Pad5)") (class "Default")
      (node (ref "IC1") (pin "5") (pinfunction "5_5") (pintype "passive"))
    )
    (net (code "70") (name "unconnected-(IC1-Pad8)") (class "Default")
      (node (ref "IC1") (pin "8") (pinfunction "8_8") (pintype "passive"))
    )
    (net (code "71") (name "unconnected-(IC1-Pad9)") (class "Default")
      (node (ref "IC1") (pin "9") (pinfunction "9_9") (pintype "passive"))
    )
    (net (code "72") (name "unconnected-(IC1-Pad11)") (class "Default")
      (node (ref "IC1") (pin "11") (pinfunction "11_11") (pintype "passive"))
    )
    (net (code "73") (name "unconnected-(IC1-Pad13)") (class "Default")
      (node (ref "IC1") (pin "13") (pinfunction "13_13") (pintype "passive"))
    )
    (net (code "74") (name "unconnected-(IC1-Pad14)") (class "Default")
      (node (ref "IC1") (pin "14") (pinfunction "14_14") (pintype "passive"))
    )
    (net (code "75") (name "unconnected-(IC1-Pad18)") (class "Default")
      (node (ref "IC1") (pin "18") (pinfunction "18_18") (pintype "passive"))
    )
    (net (code "76") (name "unconnected-(IC3B-+IN-Pad5)") (class "Default")
      (node (ref "IC3") (pin "5") (pinfunction "+IN_5") (pintype "input"))
    )
    (net (code "77") (name "unconnected-(NC-P-Pad1)") (class "Default")
      (node (ref "NC") (pin "1") (pinfunction "P_1") (pintype "bidirectional"))
    )
  )
)
